# gt-jtx-breakout-genius-ms3d.net
KiCad netlist of a schematic drawn in EAGLE
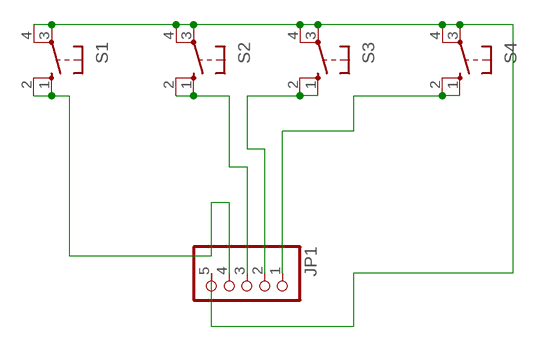
[diagram p0: schematic, sheet 1]

(export (version "E")
  (design (tool "Eeschema 10.0.6"))
  (components
    (comp (ref "JP1")
      (value "PINHD-1X5")
      (footprint "eagle-import:1X05")
      (libsource (lib "eagle-import") (part "PINHD-1X5"))
    )
    (comp (ref "S1")
      (value "10-XX")
      (footprint "eagle-import:B3F-10XX")
      (fields (field (name "MPN") "B3F-1000"))
      (libsource (lib "eagle-import") (part "10-XX"))
    )
    (comp (ref "S2")
      (value "10-XX")
      (footprint "eagle-import:B3F-10XX")
      (fields (field (name "MPN") "B3F-1000"))
      (libsource (lib "eagle-import") (part "10-XX"))
    )
    (comp (ref "S3")
      (value "10-XX")
      (footprint "eagle-import:B3F-10XX")
      (fields (field (name "MPN") "B3F-1000"))
      (libsource (lib "eagle-import") (part "10-XX"))
    )
    (comp (ref "S4")
      (value "10-XX")
      (footprint "eagle-import:B3F-10XX")
      (fields (field (name "MPN") "B3F-1000"))
      (libsource (lib "eagle-import") (part "10-XX"))
    )
  )
  (nets
    (net (code "1") (name "Net-(S1-P)") (class "Default")
      (node (ref "JP1") (pin "5") (pinfunction "5_5") (pintype "passive"))
      (node (ref "S1") (pin "3") (pinfunction "P_3") (pintype "passive"))
      (node (ref "S1") (pin "4") (pinfunction "P1_4") (pintype "passive"))
      (node (ref "S2") (pin "3") (pinfunction "P_3") (pintype "passive"))
      (node (ref "S2") (pin "4") (pinfunction "P1_4") (pintype "passive"))
      (node (ref "S3") (pin "3") (pinfunction "P_3") (pintype "passive"))
      (node (ref "S3") (pin "4") (pinfunction "P1_4") (pintype "passive"))
      (node (ref "S4") (pin "3") (pinfunction "P_3") (pintype "passive"))
      (node (ref "S4") (pin "4") (pinfunction "P1_4") (pintype "passive"))
    )
    (net (code "2") (name "Net-(S1-S)") (class "Default")
      (node (ref "JP1") (pin "4") (pinfunction "4_4") (pintype "passive"))
      (node (ref "S1") (pin "1") (pinfunction "S_1") (pintype "passive"))
      (node (ref "S1") (pin "2") (pinfunction "S1_2") (pintype "passive"))
    )
    (net (code "3") (name "Net-(S2-S)") (class "Default")
      (node (ref "JP1") (pin "3") (pinfunction "3_3") (pintype "passive"))
      (node (ref "S2") (pin "1") (pinfunction "S_1") (pintype "passive"))
      (node (ref "S2") (pin "2") (pinfunction "S1_2") (pintype "passive"))
    )
    (net (code "4") (name "Net-(S3-S)") (class "Default")
      (node (ref "JP1") (pin "2") (pinfunction "2_2") (pintype "passive"))
      (node (ref "S3") (pin "1") (pinfunction "S_1") (pintype "passive"))
      (node (ref "S3") (pin "2") (pinfunction "S1_2") (pintype "passive"))
    )
    (net (code "5") (name "Net-(S4-S)") (class "Default")
      (node (ref "JP1") (pin "1") (pinfunction "1_1") (pintype "passive"))
      (node (ref "S4") (pin "1") (pinfunction "S_1") (pintype "passive"))
      (node (ref "S4") (pin "2") (pinfunction "S1_2") (pintype "passive"))
    )
  )
)
